# DriveBoard_V2.net
KiCad netlist of a schematic drawn in Altium Designer
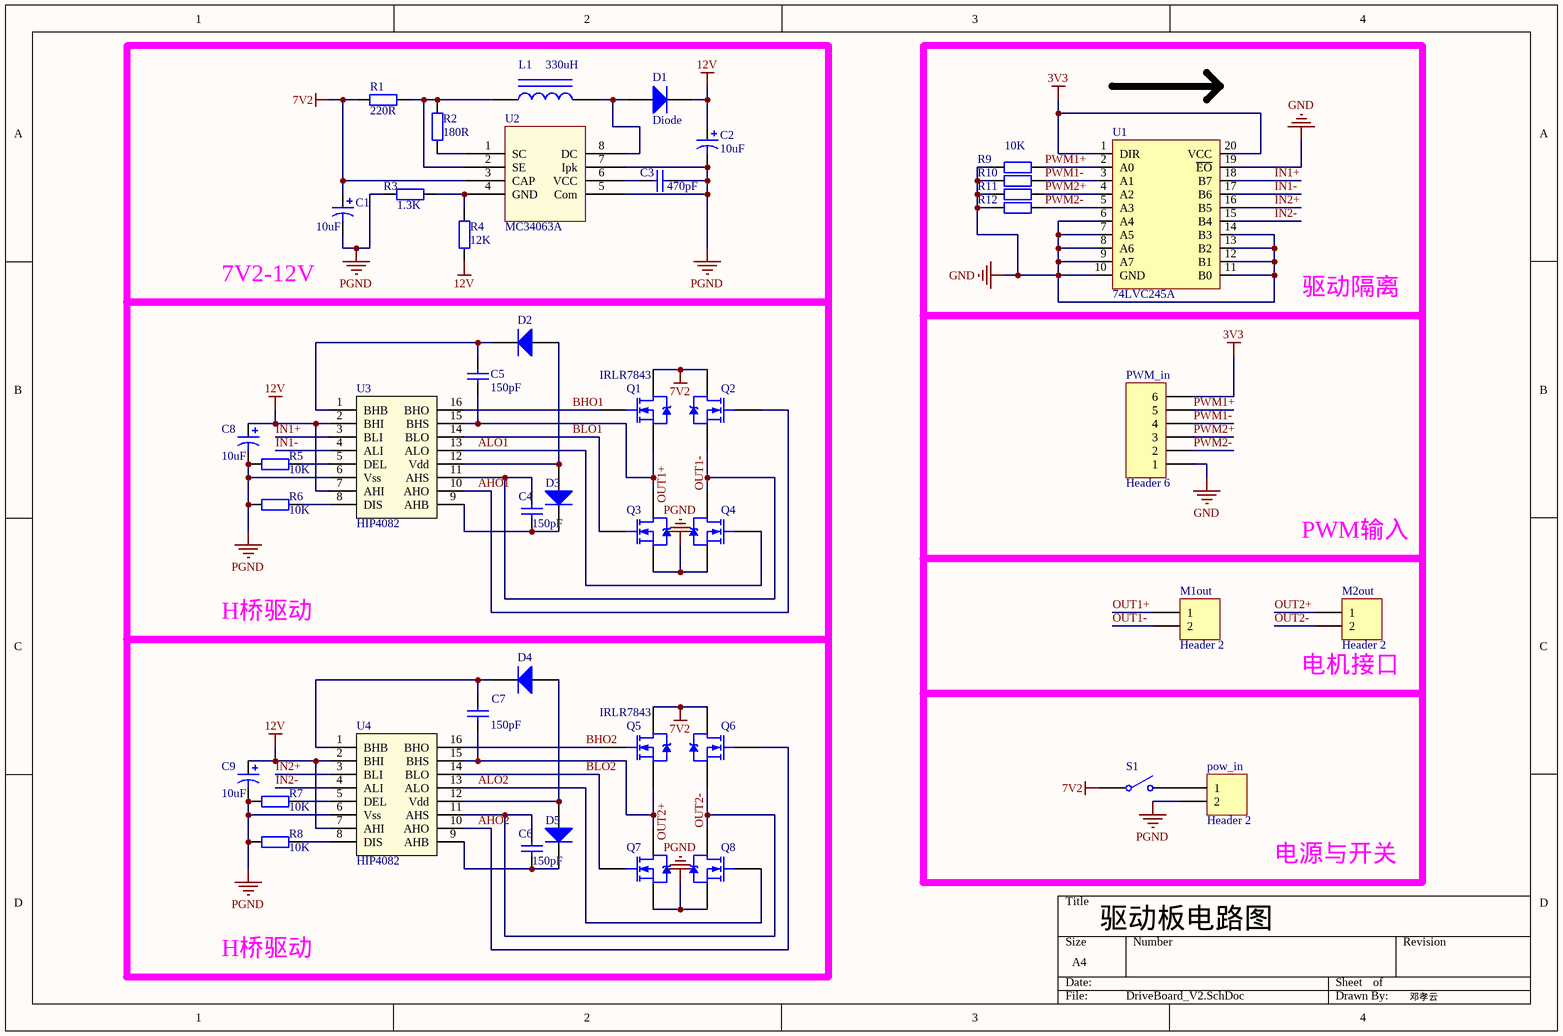
[diagram p0: DriveBoard_V2.SchDoc]

(export (version "E")
  (design (tool "Eeschema 10.0.6"))
  (components
    (comp (ref "C1")
      (value "10uF")
      (footprint "1206 C tan")
      (description "Polarized Capacitor (Radial)")
      (fields (field (name "Comment") "Cap Pol1") (field (name "PUBLISHER") "Altium Limited"))
      (libsource (lib "Miscellaneous Devices") (part "Cap Pol1"))
    )
    (comp (ref "C2")
      (value "10uF")
      (footprint "1206 C tan")
      (description "Polarized Capacitor (Radial)")
      (fields (field (name "Comment") "Cap Pol1") (field (name "PUBLISHER") "Altium Limited"))
      (libsource (lib "Miscellaneous Devices") (part "Cap Pol1"))
    )
    (comp (ref "C3")
      (value "470pF")
      (footprint "0603 C")
      (description "Capacitor")
      (fields (field (name "Comment") "Cap") (field (name "PUBLISHER") "Altium Limited"))
      (libsource (lib "Miscellaneous Devices") (part "Cap"))
    )
    (comp (ref "C4")
      (value "150pF")
      (footprint "0603 C")
      (description "Capacitor")
      (fields (field (name "Comment") "Cap") (field (name "PUBLISHER") "Altium Limited"))
      (libsource (lib "Miscellaneous Devices") (part "Cap"))
    )
    (comp (ref "C5")
      (value "150pF")
      (footprint "0603 C")
      (description "Capacitor")
      (fields (field (name "Comment") "Cap") (field (name "PUBLISHER") "Altium Limited"))
      (libsource (lib "Miscellaneous Devices") (part "Cap"))
    )
    (comp (ref "C6")
      (value "150pF")
      (footprint "0603 C")
      (description "Capacitor")
      (fields (field (name "Comment") "Cap") (field (name "PUBLISHER") "Altium Limited"))
      (libsource (lib "Miscellaneous Devices") (part "Cap"))
    )
    (comp (ref "C7")
      (value "150pF")
      (footprint "0603 C")
      (description "Capacitor")
      (fields (field (name "Comment") "Cap") (field (name "PUBLISHER") "Altium Limited"))
      (libsource (lib "Miscellaneous Devices") (part "Cap"))
    )
    (comp (ref "C8")
      (value "10uF")
      (footprint "1206 C tan")
      (description "Polarized Capacitor (Radial)")
      (fields (field (name "Comment") "Cap Pol1") (field (name "PUBLISHER") "Altium Limited"))
      (libsource (lib "Miscellaneous Devices") (part "Cap Pol1"))
    )
    (comp (ref "C9")
      (value "10uF")
      (footprint "1206 C tan")
      (description "Polarized Capacitor (Radial)")
      (fields (field (name "Comment") "Cap Pol1") (field (name "PUBLISHER") "Altium Limited"))
      (libsource (lib "Miscellaneous Devices") (part "Cap Pol1"))
    )
    (comp (ref "D1")
      (value "Diode")
      (footprint "1206 D")
      (description "Default Diode")
      (fields (field (name "PUBLISHER") "Altium Limited"))
      (libsource (lib "Miscellaneous Devices") (part "Diode"))
    )
    (comp (ref "D2")
      (value "Diode")
      (footprint "SOD-123")
      (description "Default Diode")
      (fields (field (name "PUBLISHER") "Altium Limited"))
      (libsource (lib "Miscellaneous Devices") (part "Diode"))
    )
    (comp (ref "D3")
      (value "Diode")
      (footprint "SOD-123")
      (description "Default Diode")
      (fields (field (name "PUBLISHER") "Altium Limited"))
      (libsource (lib "Miscellaneous Devices") (part "Diode"))
    )
    (comp (ref "D4")
      (value "Diode")
      (footprint "SOD-123")
      (description "Default Diode")
      (fields (field (name "PUBLISHER") "Altium Limited"))
      (libsource (lib "Miscellaneous Devices") (part "Diode"))
    )
    (comp (ref "D5")
      (value "Diode")
      (footprint "SOD-123")
      (description "Default Diode")
      (fields (field (name "PUBLISHER") "Altium Limited"))
      (libsource (lib "Miscellaneous Devices") (part "Diode"))
    )
    (comp (ref "L1")
      (value "330uH")
      (footprint "CDRH74R")
      (description "Magnetic-Core Inductor")
      (fields (field (name "Comment") "Inductor Iron") (field (name "PUBLISHER") "Altium Limited"))
      (libsource (lib "Miscellaneous Devices") (part "Inductor Iron"))
    )
    (comp (ref "M1out")
      (value "Header 2")
      (footprint "Connect 050-2")
      (description "Header, 2-Pin")
      (fields (field (name "PUBLISHER") "Altium Limited"))
      (libsource (lib "Miscellaneous Connectors") (part "Header 2"))
    )
    (comp (ref "M2out")
      (value "Header 2")
      (footprint "Connect 050-2")
      (description "Header, 2-Pin")
      (fields (field (name "PUBLISHER") "Altium Limited"))
      (libsource (lib "Miscellaneous Connectors") (part "Header 2"))
    )
    (comp (ref "pow_in")
      (value "Header 2")
      (footprint "Connect 050-2")
      (description "Header, 2-Pin")
      (fields (field (name "PUBLISHER") "Altium Limited"))
      (libsource (lib "Miscellaneous Connectors") (part "Header 2"))
    )
    (comp (ref "PWM_in")
      (value "Header 6")
      (footprint "Header P6")
      (description "Header, 6-Pin")
      (fields (field (name "PUBLISHER") "Altium Limited"))
      (libsource (lib "Miscellaneous Connectors") (part "Header 6"))
    )
    (comp (ref "Q1")
      (value "IRLR7843")
      (footprint "LR7843")
      (description "N-Channel Power MOSFET")
      (fields (field (name "PUBLISHER") "Altium Limited"))
      (libsource (lib "Miscellaneous Devices") (part "NMOS-2"))
    )
    (comp (ref "Q2")
      (value "IRLR7843")
      (footprint "LR7843")
      (description "N-Channel Power MOSFET")
      (fields (field (name "PUBLISHER") "Altium Limited"))
      (libsource (lib "Miscellaneous Devices") (part "NMOS-2"))
    )
    (comp (ref "Q3")
      (value "IRLR7843")
      (footprint "LR7843")
      (description "N-Channel Power MOSFET")
      (fields (field (name "PUBLISHER") "Altium Limited"))
      (libsource (lib "Miscellaneous Devices") (part "NMOS-2"))
    )
    (comp (ref "Q4")
      (value "IRLR7843")
      (footprint "LR7843")
      (description "N-Channel Power MOSFET")
      (fields (field (name "PUBLISHER") "Altium Limited"))
      (libsource (lib "Miscellaneous Devices") (part "NMOS-2"))
    )
    (comp (ref "Q5")
      (value "IRLR7843")
      (footprint "LR7843")
      (description "N-Channel Power MOSFET")
      (fields (field (name "PUBLISHER") "Altium Limited"))
      (libsource (lib "Miscellaneous Devices") (part "NMOS-2"))
    )
    (comp (ref "Q6")
      (value "IRLR7843")
      (footprint "LR7843")
      (description "N-Channel Power MOSFET")
      (fields (field (name "PUBLISHER") "Altium Limited"))
      (libsource (lib "Miscellaneous Devices") (part "NMOS-2"))
    )
    (comp (ref "Q7")
      (value "IRLR7843")
      (footprint "LR7843")
      (description "N-Channel Power MOSFET")
      (fields (field (name "PUBLISHER") "Altium Limited"))
      (libsource (lib "Miscellaneous Devices") (part "NMOS-2"))
    )
    (comp (ref "Q8")
      (value "IRLR7843")
      (footprint "LR7843")
      (description "N-Channel Power MOSFET")
      (fields (field (name "PUBLISHER") "Altium Limited"))
      (libsource (lib "Miscellaneous Devices") (part "NMOS-2"))
    )
    (comp (ref "R1")
      (value "220R")
      (footprint "0805 R")
      (description "Resistor")
      (fields (field (name "Comment") "Res2") (field (name "PUBLISHER") "Altium Limited"))
      (libsource (lib "") (part "Res2_3"))
    )
    (comp (ref "R2")
      (value "180R")
      (footprint "0603 R")
      (description "Resistor")
      (fields (field (name "Comment") "Res2") (field (name "PUBLISHER") "Altium Limited"))
      (libsource (lib "") (part "Res2_2"))
    )
    (comp (ref "R3")
      (value "1.3K")
      (footprint "0603 R")
      (description "Resistor")
      (fields (field (name "Comment") "Res2") (field (name "PUBLISHER") "Altium Limited"))
      (libsource (lib "") (part "Res2_1"))
    )
    (comp (ref "R4")
      (value "12K")
      (footprint "0805 R")
      (description "Resistor")
      (fields (field (name "Comment") "Res2") (field (name "PUBLISHER") "Altium Limited"))
      (libsource (lib "") (part "Res2_2"))
    )
    (comp (ref "R5")
      (value "10K")
      (footprint "0805 R")
      (description "Resistor")
      (fields (field (name "Comment") "Res2") (field (name "PUBLISHER") "Altium Limited"))
      (libsource (lib "") (part "Res2_1"))
    )
    (comp (ref "R6")
      (value "10K")
      (footprint "0805 R")
      (description "Resistor")
      (fields (field (name "Comment") "Res2") (field (name "PUBLISHER") "Altium Limited"))
      (libsource (lib "") (part "Res2_1"))
    )
    (comp (ref "R7")
      (value "10K")
      (footprint "0805 R")
      (description "Resistor")
      (fields (field (name "Comment") "Res2") (field (name "PUBLISHER") "Altium Limited"))
      (libsource (lib "") (part "Res2_1"))
    )
    (comp (ref "R8")
      (value "10K")
      (footprint "0805 R")
      (description "Resistor")
      (fields (field (name "Comment") "Res2") (field (name "PUBLISHER") "Altium Limited"))
      (libsource (lib "") (part "Res2_1"))
    )
    (comp (ref "R9")
      (value "10K")
      (footprint "0805 R")
      (description "Resistor")
      (fields (field (name "Comment") "Res2") (field (name "PUBLISHER") "Altium Limited"))
      (libsource (lib "Miscellaneous Devices") (part "Res2"))
    )
    (comp (ref "R10")
      (value "Res2")
      (footprint "0805 R")
      (description "Resistor")
      (fields (field (name "PUBLISHER") "Altium Limited"))
      (libsource (lib "Miscellaneous Devices") (part "Res2"))
    )
    (comp (ref "R11")
      (value "Res2")
      (footprint "0805 R")
      (description "Resistor")
      (fields (field (name "PUBLISHER") "Altium Limited"))
      (libsource (lib "Miscellaneous Devices") (part "Res2"))
    )
    (comp (ref "R12")
      (value "Res2")
      (footprint "0805 R")
      (description "Resistor")
      (fields (field (name "PUBLISHER") "Altium Limited"))
      (libsource (lib "Miscellaneous Devices") (part "Res2"))
    )
    (comp (ref "S1")
      (value "SW-SPST")
      (footprint "Switch")
      (description "Single-Pole, Single-Throw Switch")
      (fields (field (name "PUBLISHER") "Altium Limited"))
      (libsource (lib "Miscellaneous Devices") (part "SW-SPST"))
    )
    (comp (ref "U1") (value "74LVC245A") (footprint "SOT163-1") (libsource (lib "Sch库") (part "74LVC245A")))
    (comp (ref "U2") (value "MC34063A") (footprint "MC34063") (libsource (lib "C车外接器件") (part "MC34063A")))
    (comp (ref "U3") (value "HIP4082") (footprint "HIP4082") (libsource (lib "C车外接器件") (part "HIP4082")))
    (comp (ref "U4") (value "HIP4082") (footprint "HIP4082") (libsource (lib "C车外接器件") (part "HIP4082")))
  )
  (nets
    (net (code "1") (name "/AHO1") (class "Default")
      (node (ref "Q2") (pin "1") (pinfunction "G_1") (pintype "passive"))
      (node (ref "U3") (pin "10") (pinfunction "AHO_10") (pintype "passive"))
    )
    (net (code "2") (name "/AHO2") (class "Default")
      (node (ref "Q6") (pin "1") (pinfunction "G_1") (pintype "passive"))
      (node (ref "U4") (pin "10") (pinfunction "AHO_10") (pintype "passive"))
    )
    (net (code "3") (name "/ALO1") (class "Default")
      (node (ref "Q4") (pin "1") (pinfunction "G_1") (pintype "passive"))
      (node (ref "U3") (pin "13") (pinfunction "ALO_13") (pintype "passive"))
    )
    (net (code "4") (name "/ALO2") (class "Default")
      (node (ref "Q8") (pin "1") (pinfunction "G_1") (pintype "passive"))
      (node (ref "U4") (pin "13") (pinfunction "ALO_13") (pintype "passive"))
    )
    (net (code "5") (name "/BHO1") (class "Default")
      (node (ref "Q1") (pin "1") (pinfunction "G_1") (pintype "passive"))
      (node (ref "U3") (pin "16") (pinfunction "BHO_16") (pintype "passive"))
    )
    (net (code "6") (name "/BHO2") (class "Default")
      (node (ref "Q5") (pin "1") (pinfunction "G_1") (pintype "passive"))
      (node (ref "U4") (pin "16") (pinfunction "BHO_16") (pintype "passive"))
    )
    (net (code "7") (name "/BLO1") (class "Default")
      (node (ref "Q3") (pin "1") (pinfunction "G_1") (pintype "passive"))
      (node (ref "U3") (pin "14") (pinfunction "BLO_14") (pintype "passive"))
    )
    (net (code "8") (name "/BLO2") (class "Default")
      (node (ref "Q7") (pin "1") (pinfunction "G_1") (pintype "passive"))
      (node (ref "U4") (pin "14") (pinfunction "BLO_14") (pintype "passive"))
    )
    (net (code "9") (name "/IN1+") (class "Default")
      (node (ref "U1") (pin "18") (pinfunction "B7_18") (pintype "passive"))
      (node (ref "U3") (pin "3") (pinfunction "BLI_3") (pintype "passive"))
    )
    (net (code "10") (name "/IN1-") (class "Default")
      (node (ref "U1") (pin "17") (pinfunction "B6_17") (pintype "passive"))
      (node (ref "U3") (pin "4") (pinfunction "ALI_4") (pintype "passive"))
    )
    (net (code "11") (name "/IN2+") (class "Default")
      (node (ref "U1") (pin "16") (pinfunction "B5_16") (pintype "passive"))
      (node (ref "U4") (pin "3") (pinfunction "BLI_3") (pintype "passive"))
    )
    (net (code "12") (name "/IN2-") (class "Default")
      (node (ref "U1") (pin "15") (pinfunction "B4_15") (pintype "passive"))
      (node (ref "U4") (pin "4") (pinfunction "ALI_4") (pintype "passive"))
    )
    (net (code "13") (name "/OUT1+") (class "Default")
      (node (ref "C5") (pin "1") (pinfunction "1_1") (pintype "passive"))
      (node (ref "M1out") (pin "1") (pinfunction "1_1") (pintype "passive"))
      (node (ref "Q1") (pin "3") (pinfunction "S_3") (pintype "passive"))
      (node (ref "Q3") (pin "2") (pinfunction "D_2") (pintype "passive"))
      (node (ref "U3") (pin "15") (pinfunction "BHS_15") (pintype "passive"))
    )
    (net (code "14") (name "/OUT1-") (class "Default")
      (node (ref "C4") (pin "2") (pinfunction "2_2") (pintype "passive"))
      (node (ref "M1out") (pin "2") (pinfunction "2_2") (pintype "passive"))
      (node (ref "Q2") (pin "3") (pinfunction "S_3") (pintype "passive"))
      (node (ref "Q4") (pin "2") (pinfunction "D_2") (pintype "passive"))
      (node (ref "U3") (pin "11") (pinfunction "AHS_11") (pintype "passive"))
    )
    (net (code "15") (name "/OUT2+") (class "Default")
      (node (ref "C7") (pin "1") (pinfunction "1_1") (pintype "passive"))
      (node (ref "M2out") (pin "1") (pinfunction "1_1") (pintype "passive"))
      (node (ref "Q5") (pin "3") (pinfunction "S_3") (pintype "passive"))
      (node (ref "Q7") (pin "2") (pinfunction "D_2") (pintype "passive"))
      (node (ref "U4") (pin "15") (pinfunction "BHS_15") (pintype "passive"))
    )
    (net (code "16") (name "/OUT2-") (class "Default")
      (node (ref "C6") (pin "2") (pinfunction "2_2") (pintype "passive"))
      (node (ref "M2out") (pin "2") (pinfunction "2_2") (pintype "passive"))
      (node (ref "Q6") (pin "3") (pinfunction "S_3") (pintype "passive"))
      (node (ref "Q8") (pin "2") (pinfunction "D_2") (pintype "passive"))
      (node (ref "U4") (pin "11") (pinfunction "AHS_11") (pintype "passive"))
    )
    (net (code "17") (name "/PWM1+") (class "Default")
      (node (ref "PWM_in") (pin "5") (pinfunction "5_5") (pintype "passive"))
      (node (ref "R9") (pin "1") (pinfunction "1_1") (pintype "passive"))
      (node (ref "U1") (pin "2") (pinfunction "A0_2") (pintype "passive"))
    )
    (net (code "18") (name "/PWM1-") (class "Default")
      (node (ref "PWM_in") (pin "4") (pinfunction "4_4") (pintype "passive"))
      (node (ref "R10") (pin "1") (pinfunction "1_1") (pintype "passive"))
      (node (ref "U1") (pin "3") (pinfunction "A1_3") (pintype "passive"))
    )
    (net (code "19") (name "/PWM2+") (class "Default")
      (node (ref "PWM_in") (pin "3") (pinfunction "3_3") (pintype "passive"))
      (node (ref "R11") (pin "1") (pinfunction "1_1") (pintype "passive"))
      (node (ref "U1") (pin "4") (pinfunction "A2_4") (pintype "passive"))
    )
    (net (code "20") (name "/PWM2-") (class "Default")
      (node (ref "PWM_in") (pin "2") (pinfunction "2_2") (pintype "passive"))
      (node (ref "R12") (pin "1") (pinfunction "1_1") (pintype "passive"))
      (node (ref "U1") (pin "5") (pinfunction "A3_5") (pintype "passive"))
    )
    (net (code "21") (name "3V3") (class "Default")
      (node (ref "PWM_in") (pin "6") (pinfunction "6_6") (pintype "passive"))
      (node (ref "U1") (pin "1") (pinfunction "DIR_1") (pintype "passive"))
      (node (ref "U1") (pin "20") (pinfunction "VCC_20") (pintype "passive"))
    )
    (net (code "22") (name "7V2") (class "Default")
      (node (ref "C1") (pin "1") (pinfunction "1_1") (pintype "passive"))
      (node (ref "Q1") (pin "2") (pinfunction "D_2") (pintype "passive"))
      (node (ref "Q2") (pin "2") (pinfunction "D_2") (pintype "passive"))
      (node (ref "Q5") (pin "2") (pinfunction "D_2") (pintype "passive"))
      (node (ref "Q6") (pin "2") (pinfunction "D_2") (pintype "passive"))
      (node (ref "R1") (pin "1") (pinfunction "1_1") (pintype "passive"))
      (node (ref "S1") (pin "1") (pinfunction "COMMON_1") (pintype "passive"))
      (node (ref "U2") (pin "3") (pinfunction "CAP_3") (pintype "passive"))
    )
    (net (code "23") (name "12V") (class "Default")
      (node (ref "C2") (pin "1") (pinfunction "1_1") (pintype "passive"))
      (node (ref "C8") (pin "1") (pinfunction "1_1") (pintype "passive"))
      (node (ref "C9") (pin "1") (pinfunction "1_1") (pintype "passive"))
      (node (ref "D1") (pin "2") (pinfunction "K_2") (pintype "passive"))
      (node (ref "R4") (pin "1") (pinfunction "1_1") (pintype "passive"))
      (node (ref "U3") (pin "2") (pinfunction "BHI_2") (pintype "passive"))
      (node (ref "U3") (pin "7") (pinfunction "AHI_7") (pintype "passive"))
      (node (ref "U4") (pin "2") (pinfunction "BHI_2") (pintype "passive"))
      (node (ref "U4") (pin "7") (pinfunction "AHI_7") (pintype "passive"))
    )
    (net (code "24") (name "GND") (class "Default")
      (node (ref "PWM_in") (pin "1") (pinfunction "1_1") (pintype "passive"))
      (node (ref "R10") (pin "2") (pinfunction "2_2") (pintype "passive"))
      (node (ref "R11") (pin "2") (pinfunction "2_2") (pintype "passive"))
      (node (ref "R12") (pin "2") (pinfunction "2_2") (pintype "passive"))
      (node (ref "R9") (pin "2") (pinfunction "2_2") (pintype "passive"))
      (node (ref "U1") (pin "10") (pinfunction "GND_10") (pintype "passive"))
      (node (ref "U1") (pin "11") (pinfunction "B0_11") (pintype "passive"))
      (node (ref "U1") (pin "12") (pinfunction "B1_12") (pintype "passive"))
      (node (ref "U1") (pin "13") (pinfunction "B2_13") (pintype "passive"))
      (node (ref "U1") (pin "14") (pinfunction "B3_14") (pintype "passive"))
      (node (ref "U1") (pin "19") (pinfunction "~{EO}_19") (pintype "passive"))
      (node (ref "U1") (pin "6") (pinfunction "A4_6") (pintype "passive"))
      (node (ref "U1") (pin "7") (pinfunction "A5_7") (pintype "passive"))
      (node (ref "U1") (pin "8") (pinfunction "A6_8") (pintype "passive"))
      (node (ref "U1") (pin "9") (pinfunction "A7_9") (pintype "passive"))
    )
    (net (code "25") (name "Net-(D1-A)") (class "Default")
      (node (ref "D1") (pin "1") (pinfunction "A_1") (pintype "passive"))
      (node (ref "L1") (pin "2") (pinfunction "2_2") (pintype "passive"))
      (node (ref "U2") (pin "8") (pinfunction "DC_8") (pintype "passive"))
    )
    (net (code "26") (name "Net-(D2-A)") (class "Default")
      (node (ref "D2") (pin "1") (pinfunction "A_1") (pintype "passive"))
      (node (ref "D3") (pin "1") (pinfunction "A_1") (pintype "passive"))
      (node (ref "U3") (pin "12") (pinfunction "Vdd_12") (pintype "passive"))
    )
    (net (code "27") (name "Net-(D2-K)") (class "Default")
      (node (ref "C5") (pin "2") (pinfunction "2_2") (pintype "passive"))
      (node (ref "D2") (pin "2") (pinfunction "K_2") (pintype "passive"))
      (node (ref "U3") (pin "1") (pinfunction "BHB_1") (pintype "passive"))
    )
    (net (code "28") (name "Net-(D3-K)") (class "Default")
      (node (ref "C4") (pin "1") (pinfunction "1_1") (pintype "passive"))
      (node (ref "D3") (pin "2") (pinfunction "K_2") (pintype "passive"))
      (node (ref "U3") (pin "9") (pinfunction "AHB_9") (pintype "passive"))
    )
    (net (code "29") (name "Net-(D4-A)") (class "Default")
      (node (ref "D4") (pin "1") (pinfunction "A_1") (pintype "passive"))
      (node (ref "D5") (pin "1") (pinfunction "A_1") (pintype "passive"))
      (node (ref "U4") (pin "12") (pinfunction "Vdd_12") (pintype "passive"))
    )
    (net (code "30") (name "Net-(D4-K)") (class "Default")
      (node (ref "C7") (pin "2") (pinfunction "2_2") (pintype "passive"))
      (node (ref "D4") (pin "2") (pinfunction "K_2") (pintype "passive"))
      (node (ref "U4") (pin "1") (pinfunction "BHB_1") (pintype "passive"))
    )
    (net (code "31") (name "Net-(D5-K)") (class "Default")
      (node (ref "C6") (pin "1") (pinfunction "1_1") (pintype "passive"))
      (node (ref "D5") (pin "2") (pinfunction "K_2") (pintype "passive"))
      (node (ref "U4") (pin "9") (pinfunction "AHB_9") (pintype "passive"))
    )
    (net (code "32") (name "Net-(S1-NO)") (class "Default")
      (node (ref "S1") (pin "2") (pinfunction "NO_2") (pintype "passive"))
      (node (ref "pow_in") (pin "1") (pinfunction "1_1") (pintype "passive"))
    )
    (net (code "33") (name "Net-(U2-GND)") (class "Default")
      (node (ref "R3") (pin "1") (pinfunction "1_1") (pintype "passive"))
      (node (ref "R4") (pin "2") (pinfunction "2_2") (pintype "passive"))
      (node (ref "U2") (pin "4") (pinfunction "GND_4") (pintype "passive"))
    )
    (net (code "34") (name "Net-(U2-SC)") (class "Default")
      (node (ref "R2") (pin "1") (pinfunction "1_1") (pintype "passive"))
      (node (ref "U2") (pin "1") (pinfunction "SC_1") (pintype "passive"))
    )
    (net (code "35") (name "Net-(U2-SE)") (class "Default")
      (node (ref "L1") (pin "1") (pinfunction "1_1") (pintype "passive"))
      (node (ref "R1") (pin "2") (pinfunction "2_2") (pintype "passive"))
      (node (ref "R2") (pin "2") (pinfunction "2_2") (pintype "passive"))
      (node (ref "U2") (pin "2") (pinfunction "SE_2") (pintype "passive"))
    )
    (net (code "36") (name "Net-(U2-VCC)") (class "Default")
      (node (ref "C3") (pin "2") (pinfunction "2_2") (pintype "passive"))
      (node (ref "U2") (pin "6") (pinfunction "VCC_6") (pintype "passive"))
    )
    (net (code "37") (name "Net-(U3-DEL)") (class "Default")
      (node (ref "R5") (pin "1") (pinfunction "1_1") (pintype "passive"))
      (node (ref "U3") (pin "5") (pinfunction "DEL_5") (pintype "passive"))
    )
    (net (code "38") (name "Net-(U3-DIS)") (class "Default")
      (node (ref "R6") (pin "1") (pinfunction "1_1") (pintype "passive"))
      (node (ref "U3") (pin "8") (pinfunction "DIS_8") (pintype "passive"))
    )
    (net (code "39") (name "Net-(U4-DEL)") (class "Default")
      (node (ref "R7") (pin "1") (pinfunction "1_1") (pintype "passive"))
      (node (ref "U4") (pin "5") (pinfunction "DEL_5") (pintype "passive"))
    )
    (net (code "40") (name "Net-(U4-DIS)") (class "Default")
      (node (ref "R8") (pin "1") (pinfunction "1_1") (pintype "passive"))
      (node (ref "U4") (pin "8") (pinfunction "DIS_8") (pintype "passive"))
    )
    (net (code "41") (name "PGND") (class "Default")
      (node (ref "C1") (pin "2") (pinfunction "2_2") (pintype "passive"))
      (node (ref "C2") (pin "2") (pinfunction "2_2") (pintype "passive"))
      (node (ref "C3") (pin "1") (pinfunction "1_1") (pintype "passive"))
      (node (ref "C8") (pin "2") (pinfunction "2_2") (pintype "passive"))
      (node (ref "C9") (pin "2") (pinfunction "2_2") (pintype "passive"))
      (node (ref "Q3") (pin "3") (pinfunction "S_3") (pintype "passive"))
      (node (ref "Q4") (pin "3") (pinfunction "S_3") (pintype "passive"))
      (node (ref "Q7") (pin "3") (pinfunction "S_3") (pintype "passive"))
      (node (ref "Q8") (pin "3") (pinfunction "S_3") (pintype "passive"))
      (node (ref "R3") (pin "2") (pinfunction "2_2") (pintype "passive"))
      (node (ref "R5") (pin "2") (pinfunction "2_2") (pintype "passive"))
      (node (ref "R6") (pin "2") (pinfunction "2_2") (pintype "passive"))
      (node (ref "R7") (pin "2") (pinfunction "2_2") (pintype "passive"))
      (node (ref "R8") (pin "2") (pinfunction "2_2") (pintype "passive"))
      (node (ref "U2") (pin "5") (pinfunction "Com_5") (pintype "passive"))
      (node (ref "U2") (pin "7") (pinfunction "Ipk_7") (pintype "passive"))
      (node (ref "U3") (pin "6") (pinfunction "Vss_6") (pintype "passive"))
      (node (ref "U4") (pin "6") (pinfunction "Vss_6") (pintype "passive"))
      (node (ref "pow_in") (pin "2") (pinfunction "2_2") (pintype "passive"))
    )
  )
)
